# BPF.net
KiCad netlist of a schematic drawn in Altium Designer
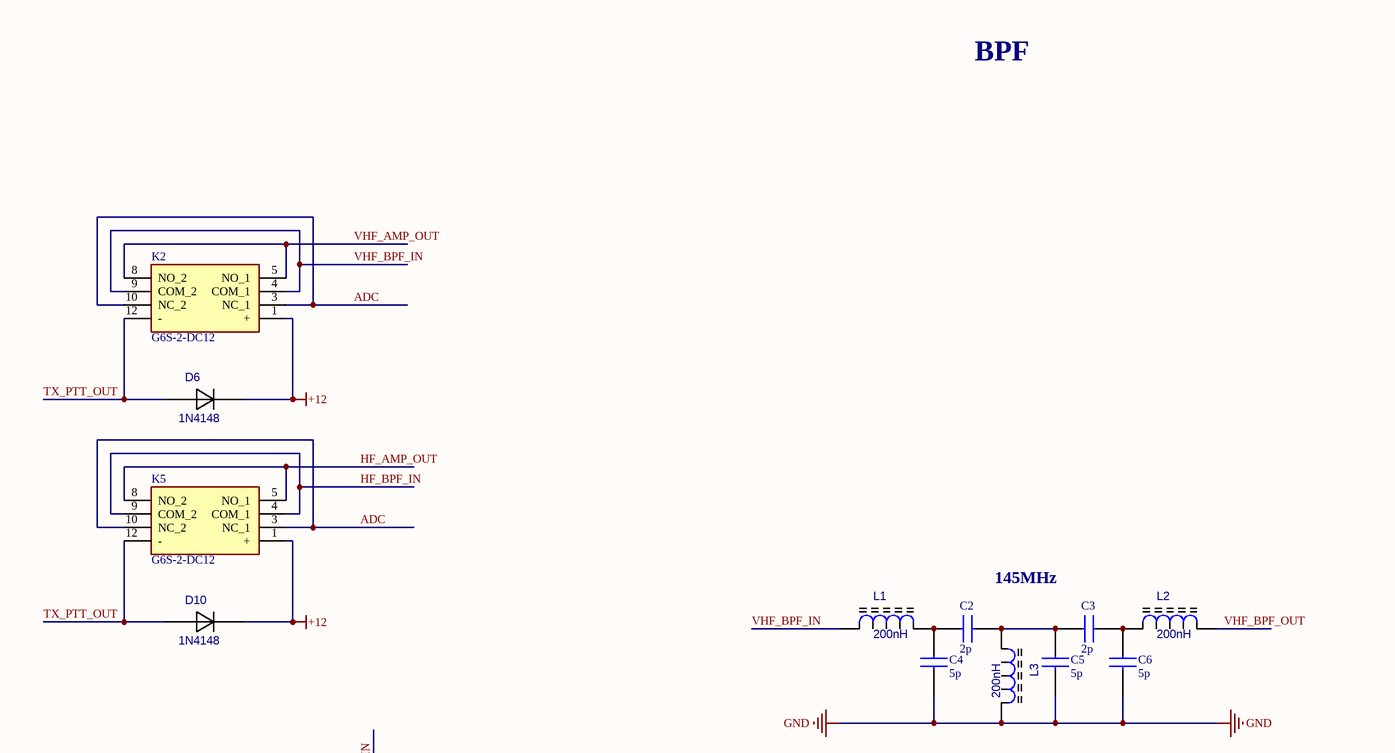
[diagram p0: BPF.SchDoc, top]
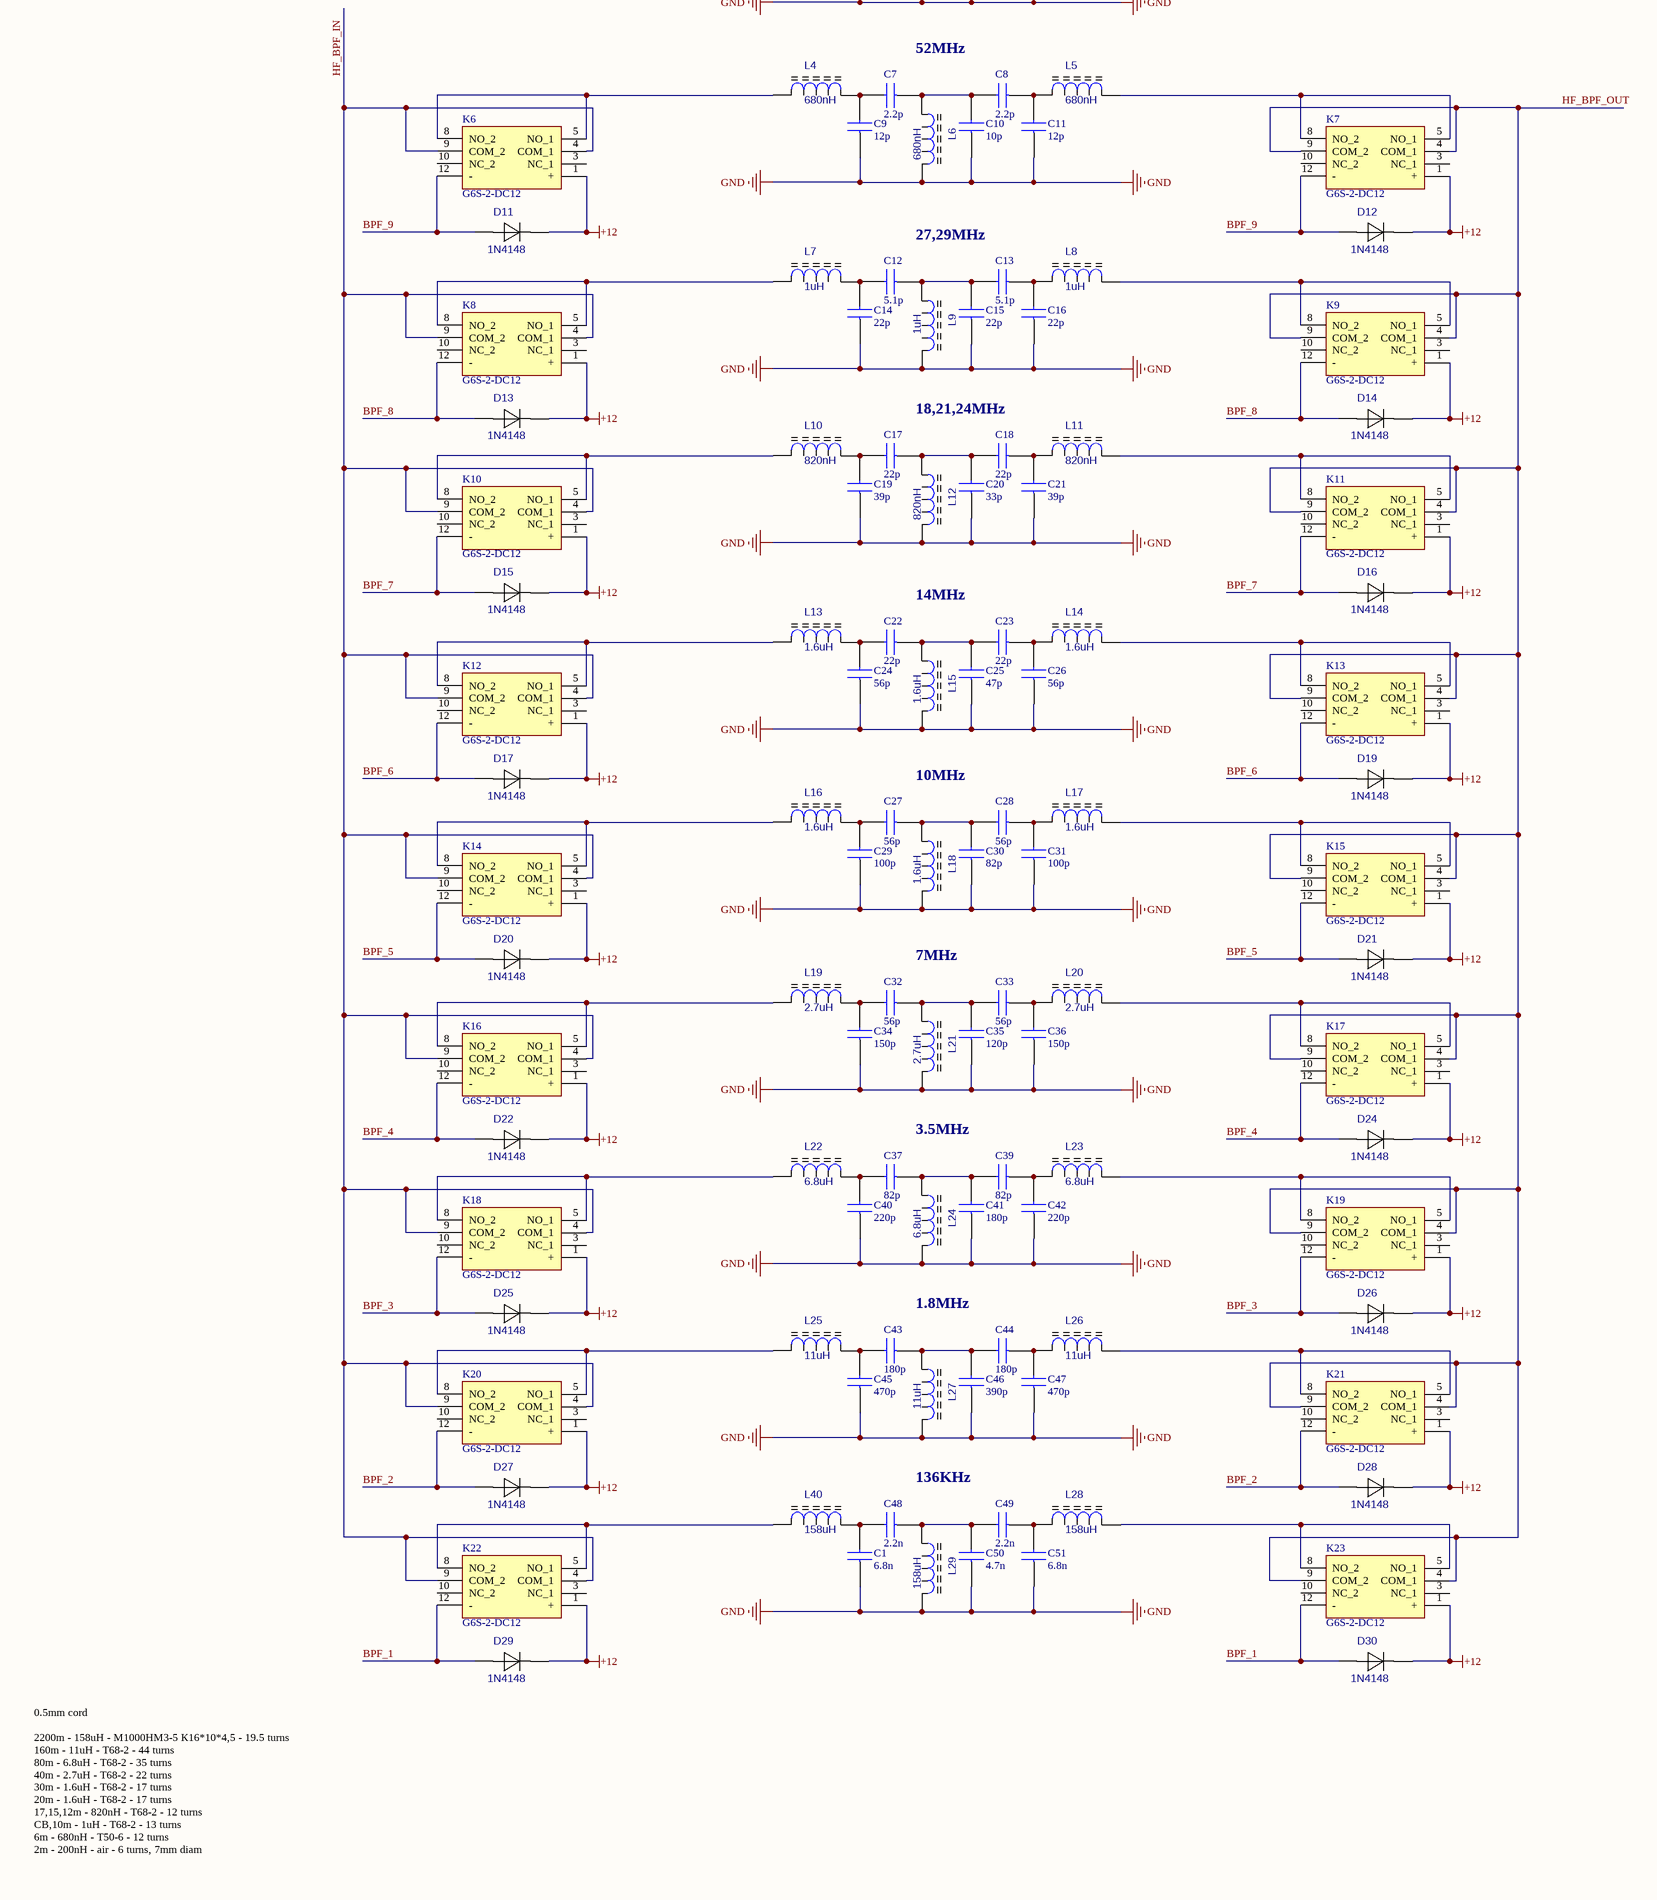
[diagram p1: BPF.SchDoc, bottom]

(export (version "E")
  (design (tool "Eeschema 10.0.6"))
  (components
    (comp (ref "C1")
      (value "6.8n")
      (footprint "CAP_1206")
      (description "Capacitor NP0 HiVolt")
      (fields
        (field (name "MANUFACTURER_PART_NUMBER") "B32620A0682J000")
        (field (name "MOUSER PART NUMBER") "871-B32620A682J")
      )
      (libsource (lib "*") (part "B32620A0682J000"))
    )
    (comp (ref "C2")
      (value "2p")
      (footprint "CAP_1206")
      (description "Capacitor NP0 HiVolt")
      (fields
        (field (name "MANUFACTURER_PART_NUMBER") "B32620A0682J000")
        (field (name "MOUSER PART NUMBER") "871-B32620A682J")
      )
      (libsource (lib "*") (part "B32620A0682J000"))
    )
    (comp (ref "C3")
      (value "2p")
      (footprint "CAP_1206")
      (description "Capacitor NP0 HiVolt")
      (fields
        (field (name "MANUFACTURER_PART_NUMBER") "B32620A0682J000")
        (field (name "MOUSER PART NUMBER") "871-B32620A682J")
      )
      (libsource (lib "*") (part "B32620A0682J000"))
    )
    (comp (ref "C4")
      (value "5p")
      (footprint "CAP_1206")
      (description "Capacitor NP0 HiVolt")
      (fields
        (field (name "MANUFACTURER_PART_NUMBER") "B32620A0682J000")
        (field (name "MOUSER PART NUMBER") "871-B32620A682J")
      )
      (libsource (lib "*") (part "B32620A0682J000"))
    )
    (comp (ref "C5")
      (value "5p")
      (footprint "CAP_1206")
      (description "Capacitor NP0 HiVolt")
      (fields
        (field (name "MANUFACTURER_PART_NUMBER") "B32620A0682J000")
        (field (name "MOUSER PART NUMBER") "871-B32620A682J")
      )
      (libsource (lib "*") (part "B32620A0682J000"))
    )
    (comp (ref "C6")
      (value "5p")
      (footprint "CAP_1206")
      (description "Capacitor NP0 HiVolt")
      (fields
        (field (name "MANUFACTURER_PART_NUMBER") "B32620A0682J000")
        (field (name "MOUSER PART NUMBER") "871-B32620A682J")
      )
      (libsource (lib "*") (part "B32620A0682J000"))
    )
    (comp (ref "C7")
      (value "2.2p")
      (footprint "CAP_1206")
      (description "Capacitor NP0 HiVolt")
      (fields
        (field (name "MANUFACTURER_PART_NUMBER") "B32620A0682J000")
        (field (name "MOUSER PART NUMBER") "871-B32620A682J")
      )
      (libsource (lib "*") (part "B32620A0682J000"))
    )
    (comp (ref "C8")
      (value "2.2p")
      (footprint "CAP_1206")
      (description "Capacitor NP0 HiVolt")
      (fields
        (field (name "MANUFACTURER_PART_NUMBER") "B32620A0682J000")
        (field (name "MOUSER PART NUMBER") "871-B32620A682J")
      )
      (libsource (lib "*") (part "B32620A0682J000"))
    )
    (comp (ref "C9")
      (value "12p")
      (footprint "CAP_1206")
      (description "Capacitor NP0 HiVolt")
      (fields
        (field (name "MANUFACTURER_PART_NUMBER") "B32620A0682J000")
        (field (name "MOUSER PART NUMBER") "871-B32620A682J")
      )
      (libsource (lib "*") (part "B32620A0682J000"))
    )
    (comp (ref "C10")
      (value "10p")
      (footprint "CAP_1206")
      (description "Capacitor NP0 HiVolt")
      (fields
        (field (name "MANUFACTURER_PART_NUMBER") "B32620A0682J000")
        (field (name "MOUSER PART NUMBER") "871-B32620A682J")
      )
      (libsource (lib "*") (part "B32620A0682J000"))
    )
    (comp (ref "C11")
      (value "12p")
      (footprint "CAP_1206")
      (description "Capacitor NP0 HiVolt")
      (fields
        (field (name "MANUFACTURER_PART_NUMBER") "B32620A0682J000")
        (field (name "MOUSER PART NUMBER") "871-B32620A682J")
      )
      (libsource (lib "*") (part "B32620A0682J000"))
    )
    (comp (ref "C12")
      (value "5.1p")
      (footprint "CAP_1206")
      (description "Capacitor NP0 HiVolt")
      (fields
        (field (name "MANUFACTURER_PART_NUMBER") "B32620A0682J000")
        (field (name "MOUSER PART NUMBER") "871-B32620A682J")
      )
      (libsource (lib "*") (part "B32620A0682J000"))
    )
    (comp (ref "C13")
      (value "5.1p")
      (footprint "CAP_1206")
      (description "Capacitor NP0 HiVolt")
      (fields
        (field (name "MANUFACTURER_PART_NUMBER") "B32620A0682J000")
        (field (name "MOUSER PART NUMBER") "871-B32620A682J")
      )
      (libsource (lib "*") (part "B32620A0682J000"))
    )
    (comp (ref "C14")
      (value "22p")
      (footprint "CAP_1206")
      (description "Capacitor NP0 HiVolt")
      (fields
        (field (name "MANUFACTURER_PART_NUMBER") "B32620A0682J000")
        (field (name "MOUSER PART NUMBER") "871-B32620A682J")
      )
      (libsource (lib "*") (part "B32620A0682J000"))
    )
    (comp (ref "C15")
      (value "22p")
      (footprint "CAP_1206")
      (description "Capacitor NP0 HiVolt")
      (fields
        (field (name "MANUFACTURER_PART_NUMBER") "B32620A0682J000")
        (field (name "MOUSER PART NUMBER") "871-B32620A682J")
      )
      (libsource (lib "*") (part "B32620A0682J000"))
    )
    (comp (ref "C16")
      (value "22p")
      (footprint "CAP_1206")
      (description "Capacitor NP0 HiVolt")
      (fields
        (field (name "MANUFACTURER_PART_NUMBER") "B32620A0682J000")
        (field (name "MOUSER PART NUMBER") "871-B32620A682J")
      )
      (libsource (lib "*") (part "B32620A0682J000"))
    )
    (comp (ref "C17")
      (value "22p")
      (footprint "CAP_1206")
      (description "Capacitor NP0 HiVolt")
      (fields
        (field (name "MANUFACTURER_PART_NUMBER") "B32620A0682J000")
        (field (name "MOUSER PART NUMBER") "871-B32620A682J")
      )
      (libsource (lib "*") (part "B32620A0682J000"))
    )
    (comp (ref "C18")
      (value "22p")
      (footprint "CAP_1206")
      (description "Capacitor NP0 HiVolt")
      (fields
        (field (name "MANUFACTURER_PART_NUMBER") "B32620A0682J000")
        (field (name "MOUSER PART NUMBER") "871-B32620A682J")
      )
      (libsource (lib "*") (part "B32620A0682J000"))
    )
    (comp (ref "C19")
      (value "39p")
      (footprint "CAP_1206")
      (description "Capacitor NP0 HiVolt")
      (fields
        (field (name "MANUFACTURER_PART_NUMBER") "B32620A0682J000")
        (field (name "MOUSER PART NUMBER") "871-B32620A682J")
      )
      (libsource (lib "*") (part "B32620A0682J000"))
    )
    (comp (ref "C20")
      (value "33p")
      (footprint "CAP_1206")
      (description "Capacitor NP0 HiVolt")
      (fields
        (field (name "MANUFACTURER_PART_NUMBER") "B32620A0682J000")
        (field (name "MOUSER PART NUMBER") "871-B32620A682J")
      )
      (libsource (lib "*") (part "B32620A0682J000"))
    )
    (comp (ref "C21")
      (value "39p")
      (footprint "CAP_1206")
      (description "Capacitor NP0 HiVolt")
      (fields
        (field (name "MANUFACTURER_PART_NUMBER") "B32620A0682J000")
        (field (name "MOUSER PART NUMBER") "871-B32620A682J")
      )
      (libsource (lib "*") (part "B32620A0682J000"))
    )
    (comp (ref "C22")
      (value "22p")
      (footprint "CAP_1206")
      (description "Capacitor NP0 HiVolt")
      (fields
        (field (name "MANUFACTURER_PART_NUMBER") "B32620A0682J000")
        (field (name "MOUSER PART NUMBER") "871-B32620A682J")
      )
      (libsource (lib "*") (part "B32620A0682J000"))
    )
    (comp (ref "C23")
      (value "22p")
      (footprint "CAP_1206")
      (description "Capacitor NP0 HiVolt")
      (fields
        (field (name "MANUFACTURER_PART_NUMBER") "B32620A0682J000")
        (field (name "MOUSER PART NUMBER") "871-B32620A682J")
      )
      (libsource (lib "*") (part "B32620A0682J000"))
    )
    (comp (ref "C24")
      (value "56p")
      (footprint "CAP_1206")
      (description "Capacitor NP0 HiVolt")
      (fields
        (field (name "MANUFACTURER_PART_NUMBER") "B32620A0682J000")
        (field (name "MOUSER PART NUMBER") "871-B32620A682J")
      )
      (libsource (lib "*") (part "B32620A0682J000"))
    )
    (comp (ref "C25")
      (value "47p")
      (footprint "CAP_1206")
      (description "Capacitor NP0 HiVolt")
      (fields
        (field (name "MANUFACTURER_PART_NUMBER") "B32620A0682J000")
        (field (name "MOUSER PART NUMBER") "871-B32620A682J")
      )
      (libsource (lib "*") (part "B32620A0682J000"))
    )
    (comp (ref "C26")
      (value "56p")
      (footprint "CAP_1206")
      (description "Capacitor NP0 HiVolt")
      (fields
        (field (name "MANUFACTURER_PART_NUMBER") "B32620A0682J000")
        (field (name "MOUSER PART NUMBER") "871-B32620A682J")
      )
      (libsource (lib "*") (part "B32620A0682J000"))
    )
    (comp (ref "C27")
      (value "56p")
      (footprint "CAP_1206")
      (description "Capacitor NP0 HiVolt")
      (fields
        (field (name "MANUFACTURER_PART_NUMBER") "B32620A0682J000")
        (field (name "MOUSER PART NUMBER") "871-B32620A682J")
      )
      (libsource (lib "*") (part "B32620A0682J000"))
    )
    (comp (ref "C28")
      (value "56p")
      (footprint "CAP_1206")
      (description "Capacitor NP0 HiVolt")
      (fields
        (field (name "MANUFACTURER_PART_NUMBER") "B32620A0682J000")
        (field (name "MOUSER PART NUMBER") "871-B32620A682J")
      )
      (libsource (lib "*") (part "B32620A0682J000"))
    )
    (comp (ref "C29")
      (value "100p")
      (footprint "CAP_1206")
      (description "Capacitor NP0 HiVolt")
      (fields
        (field (name "MANUFACTURER_PART_NUMBER") "B32620A0682J000")
        (field (name "MOUSER PART NUMBER") "871-B32620A682J")
      )
      (libsource (lib "*") (part "B32620A0682J000"))
    )
    (comp (ref "C30")
      (value "82p")
      (footprint "CAP_1206")
      (description "Capacitor NP0 HiVolt")
      (fields
        (field (name "MANUFACTURER_PART_NUMBER") "B32620A0682J000")
        (field (name "MOUSER PART NUMBER") "871-B32620A682J")
      )
      (libsource (lib "*") (part "B32620A0682J000"))
    )
    (comp (ref "C31")
      (value "100p")
      (footprint "CAP_1206")
      (description "Capacitor NP0 HiVolt")
      (fields
        (field (name "MANUFACTURER_PART_NUMBER") "B32620A0682J000")
        (field (name "MOUSER PART NUMBER") "871-B32620A682J")
      )
      (libsource (lib "*") (part "B32620A0682J000"))
    )
    (comp (ref "C32")
      (value "56p")
      (footprint "CAP_1206")
      (description "Capacitor NP0 HiVolt")
      (fields
        (field (name "MANUFACTURER_PART_NUMBER") "B32620A0682J000")
        (field (name "MOUSER PART NUMBER") "871-B32620A682J")
      )
      (libsource (lib "*") (part "B32620A0682J000"))
    )
    (comp (ref "C33")
      (value "56p")
      (footprint "CAP_1206")
      (description "Capacitor NP0 HiVolt")
      (fields
        (field (name "MANUFACTURER_PART_NUMBER") "B32620A0682J000")
        (field (name "MOUSER PART NUMBER") "871-B32620A682J")
      )
      (libsource (lib "*") (part "B32620A0682J000"))
    )
    (comp (ref "C34")
      (value "150p")
      (footprint "CAP_1206")
      (description "Capacitor NP0 HiVolt")
      (fields
        (field (name "MANUFACTURER_PART_NUMBER") "B32620A0682J000")
        (field (name "MOUSER PART NUMBER") "871-B32620A682J")
      )
      (libsource (lib "*") (part "B32620A0682J000"))
    )
    (comp (ref "C35")
      (value "120p")
      (footprint "CAP_1206")
      (description "Capacitor NP0 HiVolt")
      (fields
        (field (name "MANUFACTURER_PART_NUMBER") "B32620A0682J000")
        (field (name "MOUSER PART NUMBER") "871-B32620A682J")
      )
      (libsource (lib "*") (part "B32620A0682J000"))
    )
    (comp (ref "C36")
      (value "150p")
      (footprint "CAP_1206")
      (description "Capacitor NP0 HiVolt")
      (fields
        (field (name "MANUFACTURER_PART_NUMBER") "B32620A0682J000")
        (field (name "MOUSER PART NUMBER") "871-B32620A682J")
      )
      (libsource (lib "*") (part "B32620A0682J000"))
    )
    (comp (ref "C37")
      (value "82p")
      (footprint "CAP_1206")
      (description "Capacitor NP0 HiVolt")
      (fields
        (field (name "MANUFACTURER_PART_NUMBER") "B32620A0682J000")
        (field (name "MOUSER PART NUMBER") "871-B32620A682J")
      )
      (libsource (lib "*") (part "B32620A0682J000"))
    )
    (comp (ref "C39")
      (value "82p")
      (footprint "CAP_1206")
      (description "Capacitor NP0 HiVolt")
      (fields
        (field (name "MANUFACTURER_PART_NUMBER") "B32620A0682J000")
        (field (name "MOUSER PART NUMBER") "871-B32620A682J")
      )
      (libsource (lib "*") (part "B32620A0682J000"))
    )
    (comp (ref "C40")
      (value "220p")
      (footprint "CAP_1206")
      (description "Capacitor NP0 HiVolt")
      (fields
        (field (name "MANUFACTURER_PART_NUMBER") "B32620A0682J000")
        (field (name "MOUSER PART NUMBER") "871-B32620A682J")
      )
      (libsource (lib "*") (part "B32620A0682J000"))
    )
    (comp (ref "C41")
      (value "180p")
      (footprint "CAP_1206")
      (description "Capacitor NP0 HiVolt")
      (fields
        (field (name "MANUFACTURER_PART_NUMBER") "B32620A0682J000")
        (field (name "MOUSER PART NUMBER") "871-B32620A682J")
      )
      (libsource (lib "*") (part "B32620A0682J000"))
    )
    (comp (ref "C42")
      (value "220p")
      (footprint "CAP_1206")
      (description "Capacitor NP0 HiVolt")
      (fields
        (field (name "MANUFACTURER_PART_NUMBER") "B32620A0682J000")
        (field (name "MOUSER PART NUMBER") "871-B32620A682J")
      )
      (libsource (lib "*") (part "B32620A0682J000"))
    )
    (comp (ref "C43")
      (value "180p")
      (footprint "CAP_1206")
      (description "Capacitor NP0 HiVolt")
      (fields
        (field (name "MANUFACTURER_PART_NUMBER") "B32620A0682J000")
        (field (name "MOUSER PART NUMBER") "871-B32620A682J")
      )
      (libsource (lib "*") (part "B32620A0682J000"))
    )
    (comp (ref "C44")
      (value "180p")
      (footprint "CAP_1206")
      (description "Capacitor NP0 HiVolt")
      (fields
        (field (name "MANUFACTURER_PART_NUMBER") "B32620A0682J000")
        (field (name "MOUSER PART NUMBER") "871-B32620A682J")
      )
      (libsource (lib "*") (part "B32620A0682J000"))
    )
    (comp (ref "C45")
      (value "470p")
      (footprint "CAP_1206")
      (description "Capacitor NP0 HiVolt")
      (fields
        (field (name "MANUFACTURER_PART_NUMBER") "B32620A0682J000")
        (field (name "MOUSER PART NUMBER") "871-B32620A682J")
      )
      (libsource (lib "*") (part "B32620A0682J000"))
    )
    (comp (ref "C46")
      (value "390p")
      (footprint "CAP_1206")
      (description "Capacitor NP0 HiVolt")
      (fields
        (field (name "MANUFACTURER_PART_NUMBER") "B32620A0682J000")
        (field (name "MOUSER PART NUMBER") "871-B32620A682J")
      )
      (libsource (lib "*") (part "B32620A0682J000"))
    )
    (comp (ref "C47")
      (value "470p")
      (footprint "CAP_1206")
      (description "Capacitor NP0 HiVolt")
      (fields
        (field (name "MANUFACTURER_PART_NUMBER") "B32620A0682J000")
        (field (name "MOUSER PART NUMBER") "871-B32620A682J")
      )
      (libsource (lib "*") (part "B32620A0682J000"))
    )
    (comp (ref "C48")
      (value "2.2n")
      (footprint "CAP_1206")
      (description "Capacitor NP0 HiVolt")
      (fields
        (field (name "MANUFACTURER_PART_NUMBER") "B32620A0682J000")
        (field (name "MOUSER PART NUMBER") "871-B32620A682J")
      )
      (libsource (lib "*") (part "B32620A0682J000"))
    )
    (comp (ref "C49")
      (value "2.2n")
      (footprint "CAP_1206")
      (description "Capacitor NP0 HiVolt")
      (fields
        (field (name "MANUFACTURER_PART_NUMBER") "B32620A0682J000")
        (field (name "MOUSER PART NUMBER") "871-B32620A682J")
      )
      (libsource (lib "*") (part "B32620A0682J000"))
    )
    (comp (ref "C50")
      (value "4.7n")
      (footprint "CAP_1206")
      (description "Capacitor NP0 HiVolt")
      (fields
        (field (name "MANUFACTURER_PART_NUMBER") "B32620A0682J000")
        (field (name "MOUSER PART NUMBER") "871-B32620A682J")
      )
      (libsource (lib "*") (part "B32620A0682J000"))
    )
    (comp (ref "C51")
      (value "6.8n")
      (footprint "CAP_1206")
      (description "Capacitor NP0 HiVolt")
      (fields
        (field (name "MANUFACTURER_PART_NUMBER") "B32620A0682J000")
        (field (name "MOUSER PART NUMBER") "871-B32620A682J")
      )
      (libsource (lib "*") (part "B32620A0682J000"))
    )
    (comp (ref "D6") (value "1N4148") (footprint "SS14") (libsource (lib "RF-UNIT-BIG") (part "1N4148")))
    (comp (ref "D10") (value "1N4148") (footprint "SS14") (libsource (lib "RF-UNIT-BIG") (part "1N4148")))
    (comp (ref "D11") (value "1N4148") (footprint "SS14") (libsource (lib "RF-UNIT-BIG") (part "1N4148")))
    (comp (ref "D12") (value "1N4148") (footprint "SS14") (libsource (lib "RF-UNIT-BIG") (part "1N4148")))
    (comp (ref "D13") (value "1N4148") (footprint "SS14") (libsource (lib "RF-UNIT-BIG") (part "1N4148")))
    (comp (ref "D14") (value "1N4148") (footprint "SS14") (libsource (lib "RF-UNIT-BIG") (part "1N4148")))
    (comp (ref "D15") (value "1N4148") (footprint "SS14") (libsource (lib "RF-UNIT-BIG") (part "1N4148")))
    (comp (ref "D16") (value "1N4148") (footprint "SS14") (libsource (lib "RF-UNIT-BIG") (part "1N4148")))
    (comp (ref "D17") (value "1N4148") (footprint "SS14") (libsource (lib "RF-UNIT-BIG") (part "1N4148")))
    (comp (ref "D19") (value "1N4148") (footprint "SS14") (libsource (lib "RF-UNIT-BIG") (part "1N4148")))
    (comp (ref "D20") (value "1N4148") (footprint "SS14") (libsource (lib "RF-UNIT-BIG") (part "1N4148")))
    (comp (ref "D21") (value "1N4148") (footprint "SS14") (libsource (lib "RF-UNIT-BIG") (part "1N4148")))
    (comp (ref "D22") (value "1N4148") (footprint "SS14") (libsource (lib "RF-UNIT-BIG") (part "1N4148")))
    (comp (ref "D24") (value "1N4148") (footprint "SS14") (libsource (lib "RF-UNIT-BIG") (part "1N4148")))
    (comp (ref "D25") (value "1N4148") (footprint "SS14") (libsource (lib "RF-UNIT-BIG") (part "1N4148")))
    (comp (ref "D26") (value "1N4148") (footprint "SS14") (libsource (lib "RF-UNIT-BIG") (part "1N4148")))
    (comp (ref "D27") (value "1N4148") (footprint "SS14") (libsource (lib "RF-UNIT-BIG") (part "1N4148")))
    (comp (ref "D28") (value "1N4148") (footprint "SS14") (libsource (lib "RF-UNIT-BIG") (part "1N4148")))
    (comp (ref "D29") (value "1N4148") (footprint "SS14") (libsource (lib "RF-UNIT-BIG") (part "1N4148")))
    (comp (ref "D30") (value "1N4148") (footprint "SS14") (libsource (lib "RF-UNIT-BIG") (part "1N4148")))
    (comp (ref "K2")
      (value "G6S-2-DC12")
      (footprint "SamacSys:G6S2DC12")
      (description "Relay or Contactor")
      (fields (field (name "MOUSER PART NUMBER") "653-G6S-2-DC12A"))
      (libsource (lib "*") (part "G6S-2-DC12"))
    )
    (comp (ref "K5")
      (value "G6S-2-DC12")
      (footprint "SamacSys:G6S2DC12")
      (description "Relay or Contactor")
      (fields (field (name "MOUSER PART NUMBER") "653-G6S-2-DC12A"))
      (libsource (lib "*") (part "G6S-2-DC12"))
    )
    (comp (ref "K6")
      (value "G6S-2-DC12")
      (footprint "SamacSys:G6S2DC12")
      (description "Relay or Contactor")
      (fields (field (name "MOUSER PART NUMBER") "653-G6S-2-DC12A"))
      (libsource (lib "*") (part "G6S-2-DC12"))
    )
    (comp (ref "K7")
      (value "G6S-2-DC12")
      (footprint "SamacSys:G6S2DC12")
      (description "Relay or Contactor")
      (fields (field (name "MOUSER PART NUMBER") "653-G6S-2-DC12A"))
      (libsource (lib "*") (part "G6S-2-DC12"))
    )
    (comp (ref "K8")
      (value "G6S-2-DC12")
      (footprint "SamacSys:G6S2DC12")
      (description "Relay or Contactor")
      (fields (field (name "MOUSER PART NUMBER") "653-G6S-2-DC12A"))
      (libsource (lib "*") (part "G6S-2-DC12"))
    )
    (comp (ref "K9")
      (value "G6S-2-DC12")
      (footprint "SamacSys:G6S2DC12")
      (description "Relay or Contactor")
      (fields (field (name "MOUSER PART NUMBER") "653-G6S-2-DC12A"))
      (libsource (lib "*") (part "G6S-2-DC12"))
    )
    (comp (ref "K10")
      (value "G6S-2-DC12")
      (footprint "SamacSys:G6S2DC12")
      (description "Relay or Contactor")
      (fields (field (name "MOUSER PART NUMBER") "653-G6S-2-DC12A"))
      (libsource (lib "*") (part "G6S-2-DC12"))
    )
    (comp (ref "K11")
      (value "G6S-2-DC12")
      (footprint "SamacSys:G6S2DC12")
      (description "Relay or Contactor")
      (fields (field (name "MOUSER PART NUMBER") "653-G6S-2-DC12A"))
      (libsource (lib "*") (part "G6S-2-DC12"))
    )
    (comp (ref "K12")
      (value "G6S-2-DC12")
      (footprint "SamacSys:G6S2DC12")
      (description "Relay or Contactor")
      (fields (field (name "MOUSER PART NUMBER") "653-G6S-2-DC12A"))
      (libsource (lib "*") (part "G6S-2-DC12"))
    )
    (comp (ref "K13")
      (value "G6S-2-DC12")
      (footprint "SamacSys:G6S2DC12")
      (description "Relay or Contactor")
      (fields (field (name "MOUSER PART NUMBER") "653-G6S-2-DC12A"))
      (libsource (lib "*") (part "G6S-2-DC12"))
    )
    (comp (ref "K14")
      (value "G6S-2-DC12")
      (footprint "SamacSys:G6S2DC12")
      (description "Relay or Contactor")
      (fields (field (name "MOUSER PART NUMBER") "653-G6S-2-DC12A"))
      (libsource (lib "*") (part "G6S-2-DC12"))
    )
    (comp (ref "K15")
      (value "G6S-2-DC12")
      (footprint "SamacSys:G6S2DC12")
      (description "Relay or Contactor")
      (fields (field (name "MOUSER PART NUMBER") "653-G6S-2-DC12A"))
      (libsource (lib "*") (part "G6S-2-DC12"))
    )
    (comp (ref "K16")
      (value "G6S-2-DC12")
      (footprint "SamacSys:G6S2DC12")
      (description "Relay or Contactor")
      (fields (field (name "MOUSER PART NUMBER") "653-G6S-2-DC12A"))
      (libsource (lib "*") (part "G6S-2-DC12"))
    )
    (comp (ref "K17")
      (value "G6S-2-DC12")
      (footprint "SamacSys:G6S2DC12")
      (description "Relay or Contactor")
      (fields (field (name "MOUSER PART NUMBER") "653-G6S-2-DC12A"))
      (libsource (lib "*") (part "G6S-2-DC12"))
    )
    (comp (ref "K18")
      (value "G6S-2-DC12")
      (footprint "SamacSys:G6S2DC12")
      (description "Relay or Contactor")
      (fields (field (name "MOUSER PART NUMBER") "653-G6S-2-DC12A"))
      (libsource (lib "*") (part "G6S-2-DC12"))
    )
    (comp (ref "K19")
      (value "G6S-2-DC12")
      (footprint "SamacSys:G6S2DC12")
      (description "Relay or Contactor")
      (fields (field (name "MOUSER PART NUMBER") "653-G6S-2-DC12A"))
      (libsource (lib "*") (part "G6S-2-DC12"))
    )
    (comp (ref "K20")
      (value "G6S-2-DC12")
      (footprint "SamacSys:G6S2DC12")
      (description "Relay or Contactor")
      (fields (field (name "MOUSER PART NUMBER") "653-G6S-2-DC12A"))
      (libsource (lib "*") (part "G6S-2-DC12"))
    )
    (comp (ref "K21")
      (value "G6S-2-DC12")
      (footprint "SamacSys:G6S2DC12")
      (description "Relay or Contactor")
      (fields (field (name "MOUSER PART NUMBER") "653-G6S-2-DC12A"))
      (libsource (lib "*") (part "G6S-2-DC12"))
    )
    (comp (ref "K22")
      (value "G6S-2-DC12")
      (footprint "SamacSys:G6S2DC12")
      (description "Relay or Contactor")
      (fields (field (name "MOUSER PART NUMBER") "653-G6S-2-DC12A"))
      (libsource (lib "*") (part "G6S-2-DC12"))
    )
    (comp (ref "K23")
      (value "G6S-2-DC12")
      (footprint "SamacSys:G6S2DC12")
      (description "Relay or Contactor")
      (fields (field (name "MOUSER PART NUMBER") "653-G6S-2-DC12A"))
      (libsource (lib "*") (part "G6S-2-DC12"))
    )
    (comp (ref "L1")
      (value "200nH")
      (footprint "IND_FERRITE_CORE_1")
      (description "Inductor")
      (libsource (lib "*") (part "IND_FERRITE_CORE"))
    )
    (comp (ref "L2")
      (value "200nH")
      (footprint "IND_FERRITE_CORE_1")
      (description "Inductor")
      (libsource (lib "*") (part "IND_FERRITE_CORE"))
    )
    (comp (ref "L3")
      (value "200nH")
      (footprint "IND_FERRITE_CORE_1")
      (description "Inductor")
      (libsource (lib "*") (part "IND_FERRITE_CORE"))
    )
    (comp (ref "L4")
      (value "680nH")
      (footprint "IND_FERRITE_CORE_1")
      (description "Inductor")
      (libsource (lib "*") (part "IND_FERRITE_CORE"))
    )
    (comp (ref "L5")
      (value "680nH")
      (footprint "IND_FERRITE_CORE_1")
      (description "Inductor")
      (libsource (lib "*") (part "IND_FERRITE_CORE"))
    )
    (comp (ref "L6")
      (value "680nH")
      (footprint "IND_FERRITE_CORE_1")
      (description "Inductor")
      (libsource (lib "*") (part "IND_FERRITE_CORE"))
    )
    (comp (ref "L7")
      (value "1uH")
      (footprint "IND_FERRITE_CORE_1")
      (description "Inductor")
      (libsource (lib "*") (part "IND_FERRITE_CORE"))
    )
    (comp (ref "L8")
      (value "1uH")
      (footprint "IND_FERRITE_CORE_1")
      (description "Inductor")
      (libsource (lib "*") (part "IND_FERRITE_CORE"))
    )
    (comp (ref "L9")
      (value "1uH")
      (footprint "IND_FERRITE_CORE_1")
      (description "Inductor")
      (libsource (lib "*") (part "IND_FERRITE_CORE"))
    )
    (comp (ref "L10")
      (value "820nH")
      (footprint "IND_FERRITE_CORE_1")
      (description "Inductor")
      (libsource (lib "*") (part "IND_FERRITE_CORE"))
    )
    (comp (ref "L11")
      (value "820nH")
      (footprint "IND_FERRITE_CORE_1")
      (description "Inductor")
      (libsource (lib "*") (part "IND_FERRITE_CORE"))
    )
    (comp (ref "L12")
      (value "820nH")
      (footprint "IND_FERRITE_CORE_1")
      (description "Inductor")
      (libsource (lib "*") (part "IND_FERRITE_CORE"))
    )
    (comp (ref "L13")
      (value "1.6uH")
      (footprint "IND_FERRITE_CORE_1")
      (description "Inductor")
      (libsource (lib "*") (part "IND_FERRITE_CORE"))
    )
    (comp (ref "L14")
      (value "1.6uH")
      (footprint "IND_FERRITE_CORE_1")
      (description "Inductor")
      (libsource (lib "*") (part "IND_FERRITE_CORE"))
    )
    (comp (ref "L15")
      (value "1.6uH")
      (footprint "IND_FERRITE_CORE_1")
      (description "Inductor")
      (libsource (lib "*") (part "IND_FERRITE_CORE"))
    )
    (comp (ref "L16")
      (value "1.6uH")
      (footprint "IND_FERRITE_CORE_1")
      (description "Inductor")
      (libsource (lib "*") (part "IND_FERRITE_CORE"))
    )
    (comp (ref "L17")
      (value "1.6uH")
      (footprint "IND_FERRITE_CORE_1")
      (description "Inductor")
      (libsource (lib "*") (part "IND_FERRITE_CORE"))
    )
    (comp (ref "L18")
      (value "1.6uH")
      (footprint "IND_FERRITE_CORE_1")
      (description "Inductor")
      (libsource (lib "*") (part "IND_FERRITE_CORE"))
    )
    (comp (ref "L19")
      (value "2.7uH")
      (footprint "IND_FERRITE_CORE_1")
      (description "Inductor")
      (libsource (lib "*") (part "IND_FERRITE_CORE"))
    )
    (comp (ref "L20")
      (value "2.7uH")
      (footprint "IND_FERRITE_CORE_1")
      (description "Inductor")
      (libsource (lib "*") (part "IND_FERRITE_CORE"))
    )
    (comp (ref "L21")
      (value "2.7uH")
      (footprint "IND_FERRITE_CORE_1")
      (description "Inductor")
      (libsource (lib "*") (part "IND_FERRITE_CORE"))
    )
    (comp (ref "L22")
      (value "6.8uH")
      (footprint "IND_FERRITE_CORE_1")
      (description "Inductor")
      (libsource (lib "*") (part "IND_FERRITE_CORE"))
    )
    (comp (ref "L23")
      (value "6.8uH")
      (footprint "IND_FERRITE_CORE_1")
      (description "Inductor")
      (libsource (lib "*") (part "IND_FERRITE_CORE"))
    )
    (comp (ref "L24")
      (value "6.8uH")
      (footprint "IND_FERRITE_CORE_1")
      (description "Inductor")
      (libsource (lib "*") (part "IND_FERRITE_CORE"))
    )
    (comp (ref "L25")
      (value "11uH")
      (footprint "IND_FERRITE_CORE_1")
      (description "Inductor")
      (libsource (lib "*") (part "IND_FERRITE_CORE"))
    )
    (comp (ref "L26")
      (value "11uH")
      (footprint "IND_FERRITE_CORE_1")
      (description "Inductor")
      (libsource (lib "*") (part "IND_FERRITE_CORE"))
    )
    (comp (ref "L27")
      (value "11uH")
      (footprint "IND_FERRITE_CORE_1")
      (description "Inductor")
      (libsource (lib "*") (part "IND_FERRITE_CORE"))
    )
    (comp (ref "L28")
      (value "158uH")
      (footprint "IND_FERRITE_CORE_1")
      (description "Inductor")
      (libsource (lib "*") (part "IND_FERRITE_CORE"))
    )
    (comp (ref "L29")
      (value "158uH")
      (footprint "IND_FERRITE_CORE_1")
      (description "Inductor")
      (libsource (lib "*") (part "IND_FERRITE_CORE"))
    )
    (comp (ref "L40")
      (value "158uH")
      (footprint "IND_FERRITE_CORE_1")
      (description "Inductor")
      (libsource (lib "*") (part "IND_FERRITE_CORE"))
    )
  )
  (nets
    (net (code "1") (name "+12") (class "Default")
      (node (ref "D10") (pin "1") (pinfunction "K_1") (pintype "passive"))
      (node (ref "D11") (pin "1") (pinfunction "K_1") (pintype "passive"))
      (node (ref "D12") (pin "1") (pinfunction "K_1") (pintype "passive"))
      (node (ref "D13") (pin "1") (pinfunction "K_1") (pintype "passive"))
      (node (ref "D14") (pin "1") (pinfunction "K_1") (pintype "passive"))
      (node (ref "D15") (pin "1") (pinfunction "K_1") (pintype "passive"))
      (node (ref "D16") (pin "1") (pinfunction "K_1") (pintype "passive"))
      (node (ref "D17") (pin "1") (pinfunction "K_1") (pintype "passive"))
      (node (ref "D19") (pin "1") (pinfunction "K_1") (pintype "passive"))
      (node (ref "D20") (pin "1") (pinfunction "K_1") (pintype "passive"))
      (node (ref "D21") (pin "1") (pinfunction "K_1") (pintype "passive"))
      (node (ref "D22") (pin "1") (pinfunction "K_1") (pintype "passive"))
      (node (ref "D24") (pin "1") (pinfunction "K_1") (pintype "passive"))
      (node (ref "D25") (pin "1") (pinfunction "K_1") (pintype "passive"))
      (node (ref "D26") (pin "1") (pinfunction "K_1") (pintype "passive"))
      (node (ref "D27") (pin "1") (pinfunction "K_1") (pintype "passive"))
      (node (ref "D28") (pin "1") (pinfunction "K_1") (pintype "passive"))
      (node (ref "D29") (pin "1") (pinfunction "K_1") (pintype "passive"))
      (node (ref "D30") (pin "1") (pinfunction "K_1") (pintype "passive"))
      (node (ref "D6") (pin "1") (pinfunction "K_1") (pintype "passive"))
      (node (ref "K10") (pin "1") (pinfunction "+_1") (pintype "passive"))
      (node (ref "K11") (pin "1") (pinfunction "+_1") (pintype "passive"))
      (node (ref "K12") (pin "1") (pinfunction "+_1") (pintype "passive"))
      (node (ref "K13") (pin "1") (pinfunction "+_1") (pintype "passive"))
      (node (ref "K14") (pin "1") (pinfunction "+_1") (pintype "passive"))
      (node (ref "K15") (pin "1") (pinfunction "+_1") (pintype "passive"))
      (node (ref "K16") (pin "1") (pinfunction "+_1") (pintype "passive"))
      (node (ref "K17") (pin "1") (pinfunction "+_1") (pintype "passive"))
      (node (ref "K18") (pin "1") (pinfunction "+_1") (pintype "passive"))
      (node (ref "K19") (pin "1") (pinfunction "+_1") (pintype "passive"))
      (node (ref "K2") (pin "1") (pinfunction "+_1") (pintype "passive"))
      (node (ref "K20") (pin "1") (pinfunction "+_1") (pintype "passive"))
      (node (ref "K21") (pin "1") (pinfunction "+_1") (pintype "passive"))
      (node (ref "K22") (pin "1") (pinfunction "+_1") (pintype "passive"))
      (node (ref "K23") (pin "1") (pinfunction "+_1") (pintype "passive"))
      (node (ref "K5") (pin "1") (pinfunction "+_1") (pintype "passive"))
      (node (ref "K6") (pin "1") (pinfunction "+_1") (pintype "passive"))
      (node (ref "K7") (pin "1") (pinfunction "+_1") (pintype "passive"))
      (node (ref "K8") (pin "1") (pinfunction "+_1") (pintype "passive"))
      (node (ref "K9") (pin "1") (pinfunction "+_1") (pintype "passive"))
    )
    (net (code "2") (name "/ADC") (class "Default")
      (node (ref "K2") (pin "10") (pinfunction "NC_2_10") (pintype "passive"))
      (node (ref "K2") (pin "3") (pinfunction "NC_1_3") (pintype "passive"))
      (node (ref "K5") (pin "10") (pinfunction "NC_2_10") (pintype "passive"))
      (node (ref "K5") (pin "3") (pinfunction "NC_1_3") (pintype "passive"))
    )
    (net (code "3") (name "/BPF_1") (class "Default")
      (node (ref "D29") (pin "2") (pinfunction "A_2") (pintype "passive"))
      (node (ref "D30") (pin "2") (pinfunction "A_2") (pintype "passive"))
      (node (ref "K22") (pin "12") (pinfunction "-_12") (pintype "passive"))
      (node (ref "K23") (pin "12") (pinfunction "-_12") (pintype "passive"))
    )
    (net (code "4") (name "/BPF_2") (class "Default")
      (node (ref "D27") (pin "2") (pinfunction "A_2") (pintype "passive"))
      (node (ref "D28") (pin "2") (pinfunction "A_2") (pintype "passive"))
      (node (ref "K20") (pin "12") (pinfunction "-_12") (pintype "passive"))
      (node (ref "K21") (pin "12") (pinfunction "-_12") (pintype "passive"))
    )
    (net (code "5") (name "/BPF_3") (class "Default")
      (node (ref "D25") (pin "2") (pinfunction "A_2") (pintype "passive"))
      (node (ref "D26") (pin "2") (pinfunction "A_2") (pintype "passive"))
      (node (ref "K18") (pin "12") (pinfunction "-_12") (pintype "passive"))
      (node (ref "K19") (pin "12") (pinfunction "-_12") (pintype "passive"))
    )
    (net (code "6") (name "/BPF_4") (class "Default")
      (node (ref "D22") (pin "2") (pinfunction "A_2") (pintype "passive"))
      (node (ref "D24") (pin "2") (pinfunction "A_2") (pintype "passive"))
      (node (ref "K16") (pin "12") (pinfunction "-_12") (pintype "passive"))
      (node (ref "K17") (pin "12") (pinfunction "-_12") (pintype "passive"))
    )
    (net (code "7") (name "/BPF_5") (class "Default")
      (node (ref "D20") (pin "2") (pinfunction "A_2") (pintype "passive"))
      (node (ref "D21") (pin "2") (pinfunction "A_2") (pintype "passive"))
      (node (ref "K14") (pin "12") (pinfunction "-_12") (pintype "passive"))
      (node (ref "K15") (pin "12") (pinfunction "-_12") (pintype "passive"))
    )
    (net (code "8") (name "/BPF_6") (class "Default")
      (node (ref "D17") (pin "2") (pinfunction "A_2") (pintype "passive"))
      (node (ref "D19") (pin "2") (pinfunction "A_2") (pintype "passive"))
      (node (ref "K12") (pin "12") (pinfunction "-_12") (pintype "passive"))
      (node (ref "K13") (pin "12") (pinfunction "-_12") (pintype "passive"))
    )
    (net (code "9") (name "/BPF_7") (class "Default")
      (node (ref "D15") (pin "2") (pinfunction "A_2") (pintype "passive"))
      (node (ref "D16") (pin "2") (pinfunction "A_2") (pintype "passive"))
      (node (ref "K10") (pin "12") (pinfunction "-_12") (pintype "passive"))
      (node (ref "K11") (pin "12") (pinfunction "-_12") (pintype "passive"))
    )
    (net (code "10") (name "/BPF_8") (class "Default")
      (node (ref "D13") (pin "2") (pinfunction "A_2") (pintype "passive"))
      (node (ref "D14") (pin "2") (pinfunction "A_2") (pintype "passive"))
      (node (ref "K8") (pin "12") (pinfunction "-_12") (pintype "passive"))
      (node (ref "K9") (pin "12") (pinfunction "-_12") (pintype "passive"))
    )
    (net (code "11") (name "/BPF_9") (class "Default")
      (node (ref "D11") (pin "2") (pinfunction "A_2") (pintype "passive"))
      (node (ref "D12") (pin "2") (pinfunction "A_2") (pintype "passive"))
      (node (ref "K6") (pin "12") (pinfunction "-_12") (pintype "passive"))
      (node (ref "K7") (pin "12") (pinfunction "-_12") (pintype "passive"))
    )
    (net (code "12") (name "/HF_AMP_OUT") (class "Default")
      (node (ref "K5") (pin "5") (pinfunction "NO_1_5") (pintype "passive"))
      (node (ref "K5") (pin "8") (pinfunction "NO_2_8") (pintype "passive"))
    )
    (net (code "13") (name "/HF_BPF_IN") (class "Default")
      (node (ref "K10") (pin "4") (pinfunction "COM_1_4") (pintype "passive"))
      (node (ref "K10") (pin "9") (pinfunction "COM_2_9") (pintype "passive"))
      (node (ref "K12") (pin "4") (pinfunction "COM_1_4") (pintype "passive"))
      (node (ref "K12") (pin "9") (pinfunction "COM_2_9") (pintype "passive"))
      (node (ref "K14") (pin "4") (pinfunction "COM_1_4") (pintype "passive"))
      (node (ref "K14") (pin "9") (pinfunction "COM_2_9") (pintype "passive"))
      (node (ref "K16") (pin "4") (pinfunction "COM_1_4") (pintype "passive"))
      (node (ref "K16") (pin "9") (pinfunction "COM_2_9") (pintype "passive"))
      (node (ref "K18") (pin "4") (pinfunction "COM_1_4") (pintype "passive"))
      (node (ref "K18") (pin "9") (pinfunction "COM_2_9") (pintype "passive"))
      (node (ref "K20") (pin "4") (pinfunction "COM_1_4") (pintype "passive"))
      (node (ref "K20") (pin "9") (pinfunction "COM_2_9") (pintype "passive"))
      (node (ref "K22") (pin "4") (pinfunction "COM_1_4") (pintype "passive"))
      (node (ref "K22") (pin "9") (pinfunction "COM_2_9") (pintype "passive"))
      (node (ref "K5") (pin "4") (pinfunction "COM_1_4") (pintype "passive"))
      (node (ref "K5") (pin "9") (pinfunction "COM_2_9") (pintype "passive"))
      (node (ref "K6") (pin "4") (pinfunction "COM_1_4") (pintype "passive"))
      (node (ref "K6") (pin "9") (pinfunction "COM_2_9") (pintype "passive"))
      (node (ref "K8") (pin "4") (pinfunction "COM_1_4") (pintype "passive"))
      (node (ref "K8") (pin "9") (pinfunction "COM_2_9") (pintype "passive"))
    )
    (net (code "14") (name "/HF_BPF_OUT") (class "Default")
      (node (ref "K11") (pin "4") (pinfunction "COM_1_4") (pintype "passive"))
      (node (ref "K11") (pin "9") (pinfunction "COM_2_9") (pintype "passive"))
      (node (ref "K13") (pin "4") (pinfunction "COM_1_4") (pintype "passive"))
      (node (ref "K13") (pin "9") (pinfunction "COM_2_9") (pintype "passive"))
      (node (ref "K15") (pin "4") (pinfunction "COM_1_4") (pintype "passive"))
      (node (ref "K15") (pin "9") (pinfunction "COM_2_9") (pintype "passive"))
      (node (ref "K17") (pin "4") (pinfunction "COM_1_4") (pintype "passive"))
      (node (ref "K17") (pin "9") (pinfunction "COM_2_9") (pintype "passive"))
      (node (ref "K19") (pin "4") (pinfunction "COM_1_4") (pintype "passive"))
      (node (ref "K19") (pin "9") (pinfunction "COM_2_9") (pintype "passive"))
      (node (ref "K21") (pin "4") (pinfunction "COM_1_4") (pintype "passive"))
      (node (ref "K21") (pin "9") (pinfunction "COM_2_9") (pintype "passive"))
      (node (ref "K23") (pin "4") (pinfunction "COM_1_4") (pintype "passive"))
      (node (ref "K23") (pin "9") (pinfunction "COM_2_9") (pintype "passive"))
      (node (ref "K7") (pin "4") (pinfunction "COM_1_4") (pintype "passive"))
      (node (ref "K7") (pin "9") (pinfunction "COM_2_9") (pintype "passive"))
      (node (ref "K9") (pin "4") (pinfunction "COM_1_4") (pintype "passive"))
      (node (ref "K9") (pin "9") (pinfunction "COM_2_9") (pintype "passive"))
    )
    (net (code "15") (name "/TX_PTT_OUT") (class "Default")
      (node (ref "D10") (pin "2") (pinfunction "A_2") (pintype "passive"))
      (node (ref "D6") (pin "2") (pinfunction "A_2") (pintype "passive"))
      (node (ref "K2") (pin "12") (pinfunction "-_12") (pintype "passive"))
      (node (ref "K5") (pin "12") (pinfunction "-_12") (pintype "passive"))
    )
    (net (code "16") (name "/VHF_AMP_OUT") (class "Default")
      (node (ref "K2") (pin "5") (pinfunction "NO_1_5") (pintype "passive"))
      (node (ref "K2") (pin "8") (pinfunction "NO_2_8") (pintype "passive"))
    )
    (net (code "17") (name "/VHF_BPF_IN") (class "Default")
      (node (ref "K2") (pin "4") (pinfunction "COM_1_4") (pintype "passive"))
      (node (ref "K2") (pin "9") (pinfunction "COM_2_9") (pintype "passive"))
      (node (ref "L1") (pin "1") (pinfunction "A_1") (pintype "passive"))
    )
    (net (code "18") (name "/VHF_BPF_OUT") (class "Default")
      (node (ref "L2") (pin "2") (pinfunction "B_2") (pintype "passive"))
    )
    (net (code "19") (name "GND") (class "Default")
      (node (ref "C1") (pin "1") (pinfunction "1_1") (pintype "passive"))
      (node (ref "C10") (pin "1") (pinfunction "1_1") (pintype "passive"))
      (node (ref "C11") (pin "1") (pinfunction "1_1") (pintype "passive"))
      (node (ref "C14") (pin "1") (pinfunction "1_1") (pintype "passive"))
      (node (ref "C15") (pin "1") (pinfunction "1_1") (pintype "passive"))
      (node (ref "C16") (pin "1") (pinfunction "1_1") (pintype "passive"))
      (node (ref "C19") (pin "1") (pinfunction "1_1") (pintype "passive"))
      (node (ref "C20") (pin "1") (pinfunction "1_1") (pintype "passive"))
      (node (ref "C21") (pin "1") (pinfunction "1_1") (pintype "passive"))
      (node (ref "C24") (pin "1") (pinfunction "1_1") (pintype "passive"))
      (node (ref "C25") (pin "1") (pinfunction "1_1") (pintype "passive"))
      (node (ref "C26") (pin "1") (pinfunction "1_1") (pintype "passive"))
      (node (ref "C29") (pin "1") (pinfunction "1_1") (pintype "passive"))
      (node (ref "C30") (pin "1") (pinfunction "1_1") (pintype "passive"))
      (node (ref "C31") (pin "1") (pinfunction "1_1") (pintype "passive"))
      (node (ref "C34") (pin "1") (pinfunction "1_1") (pintype "passive"))
      (node (ref "C35") (pin "1") (pinfunction "1_1") (pintype "passive"))
      (node (ref "C36") (pin "1") (pinfunction "1_1") (pintype "passive"))
      (node (ref "C4") (pin "1") (pinfunction "1_1") (pintype "passive"))
      (node (ref "C40") (pin "1") (pinfunction "1_1") (pintype "passive"))
      (node (ref "C41") (pin "1") (pinfunction "1_1") (pintype "passive"))
      (node (ref "C42") (pin "1") (pinfunction "1_1") (pintype "passive"))
      (node (ref "C45") (pin "1") (pinfunction "1_1") (pintype "passive"))
      (node (ref "C46") (pin "1") (pinfunction "1_1") (pintype "passive"))
      (node (ref "C47") (pin "1") (pinfunction "1_1") (pintype "passive"))
      (node (ref "C5") (pin "1") (pinfunction "1_1") (pintype "passive"))
      (node (ref "C50") (pin "1") (pinfunction "1_1") (pintype "passive"))
      (node (ref "C51") (pin "1") (pinfunction "1_1") (pintype "passive"))
      (node (ref "C6") (pin "1") (pinfunction "1_1") (pintype "passive"))
      (node (ref "C9") (pin "1") (pinfunction "1_1") (pintype "passive"))
      (node (ref "L12") (pin "2") (pinfunction "B_2") (pintype "passive"))
      (node (ref "L15") (pin "2") (pinfunction "B_2") (pintype "passive"))
      (node (ref "L18") (pin "2") (pinfunction "B_2") (pintype "passive"))
      (node (ref "L21") (pin "2") (pinfunction "B_2") (pintype "passive"))
      (node (ref "L24") (pin "2") (pinfunction "B_2") (pintype "passive"))
      (node (ref "L27") (pin "2") (pinfunction "B_2") (pintype "passive"))
      (node (ref "L29") (pin "2") (pinfunction "B_2") (pintype "passive"))
      (node (ref "L3") (pin "2") (pinfunction "B_2") (pintype "passive"))
      (node (ref "L6") (pin "2") (pinfunction "B_2") (pintype "passive"))
      (node (ref "L9") (pin "2") (pinfunction "B_2") (pintype "passive"))
    )
    (net (code "20") (name "Net-(K6-NO_1)") (class "Default")
      (node (ref "K6") (pin "5") (pinfunction "NO_1_5") (pintype "passive"))
      (node (ref "K6") (pin "8") (pinfunction "NO_2_8") (pintype "passive"))
      (node (ref "L4") (pin "1") (pinfunction "A_1") (pintype "passive"))
    )
    (net (code "21") (name "Net-(K7-NO_1)") (class "Default")
      (node (ref "K7") (pin "5") (pinfunction "NO_1_5") (pintype "passive"))
      (node (ref "K7") (pin "8") (pinfunction "NO_2_8") (pintype "passive"))
      (node (ref "L5") (pin "2") (pinfunction "B_2") (pintype "passive"))
    )
    (net (code "22") (name "Net-(K8-NO_1)") (class "Default")
      (node (ref "K8") (pin "5") (pinfunction "NO_1_5") (pintype "passive"))
      (node (ref "K8") (pin "8") (pinfunction "NO_2_8") (pintype "passive"))
      (node (ref "L7") (pin "1") (pinfunction "A_1") (pintype "passive"))
    )
    (net (code "23") (name "Net-(K9-NO_1)") (class "Default")
      (node (ref "K9") (pin "5") (pinfunction "NO_1_5") (pintype "passive"))
      (node (ref "K9") (pin "8") (pinfunction "NO_2_8") (pintype "passive"))
      (node (ref "L8") (pin "2") (pinfunction "B_2") (pintype "passive"))
    )
    (net (code "24") (name "Net-(K10-NO_1)") (class "Default")
      (node (ref "K10") (pin "5") (pinfunction "NO_1_5") (pintype "passive"))
      (node (ref "K10") (pin "8") (pinfunction "NO_2_8") (pintype "passive"))
      (node (ref "L10") (pin "1") (pinfunction "A_1") (pintype "passive"))
    )
    (net (code "25") (name "Net-(K11-NO_1)") (class "Default")
      (node (ref "K11") (pin "5") (pinfunction "NO_1_5") (pintype "passive"))
      (node (ref "K11") (pin "8") (pinfunction "NO_2_8") (pintype "passive"))
      (node (ref "L11") (pin "2") (pinfunction "B_2") (pintype "passive"))
    )
    (net (code "26") (name "Net-(K12-NO_1)") (class "Default")
      (node (ref "K12") (pin "5") (pinfunction "NO_1_5") (pintype "passive"))
      (node (ref "K12") (pin "8") (pinfunction "NO_2_8") (pintype "passive"))
      (node (ref "L13") (pin "1") (pinfunction "A_1") (pintype "passive"))
    )
    (net (code "27") (name "Net-(K13-NO_1)") (class "Default")
      (node (ref "K13") (pin "5") (pinfunction "NO_1_5") (pintype "passive"))
      (node (ref "K13") (pin "8") (pinfunction "NO_2_8") (pintype "passive"))
      (node (ref "L14") (pin "2") (pinfunction "B_2") (pintype "passive"))
    )
    (net (code "28") (name "Net-(K14-NO_1)") (class "Default")
      (node (ref "K14") (pin "5") (pinfunction "NO_1_5") (pintype "passive"))
      (node (ref "K14") (pin "8") (pinfunction "NO_2_8") (pintype "passive"))
      (node (ref "L16") (pin "1") (pinfunction "A_1") (pintype "passive"))
    )
    (net (code "29") (name "Net-(K15-NO_1)") (class "Default")
      (node (ref "K15") (pin "5") (pinfunction "NO_1_5") (pintype "passive"))
      (node (ref "K15") (pin "8") (pinfunction "NO_2_8") (pintype "passive"))
      (node (ref "L17") (pin "2") (pinfunction "B_2") (pintype "passive"))
    )
    (net (code "30") (name "Net-(K16-NO_1)") (class "Default")
      (node (ref "K16") (pin "5") (pinfunction "NO_1_5") (pintype "passive"))
      (node (ref "K16") (pin "8") (pinfunction "NO_2_8") (pintype "passive"))
      (node (ref "L19") (pin "1") (pinfunction "A_1") (pintype "passive"))
    )
    (net (code "31") (name "Net-(K17-NO_1)") (class "Default")
      (node (ref "K17") (pin "5") (pinfunction "NO_1_5") (pintype "passive"))
      (node (ref "K17") (pin "8") (pinfunction "NO_2_8") (pintype "passive"))
      (node (ref "L20") (pin "2") (pinfunction "B_2") (pintype "passive"))
    )
    (net (code "32") (name "Net-(K18-NO_1)") (class "Default")
      (node (ref "K18") (pin "5") (pinfunction "NO_1_5") (pintype "passive"))
      (node (ref "K18") (pin "8") (pinfunction "NO_2_8") (pintype "passive"))
      (node (ref "L22") (pin "1") (pinfunction "A_1") (pintype "passive"))
    )
    (net (code "33") (name "Net-(K19-NO_1)") (class "Default")
      (node (ref "K19") (pin "5") (pinfunction "NO_1_5") (pintype "passive"))
      (node (ref "K19") (pin "8") (pinfunction "NO_2_8") (pintype "passive"))
      (node (ref "L23") (pin "2") (pinfunction "B_2") (pintype "passive"))
    )
    (net (code "34") (name "Net-(K20-NO_1)") (class "Default")
      (node (ref "K20") (pin "5") (pinfunction "NO_1_5") (pintype "passive"))
      (node (ref "K20") (pin "8") (pinfunction "NO_2_8") (pintype "passive"))
      (node (ref "L25") (pin "1") (pinfunction "A_1") (pintype "passive"))
    )
    (net (code "35") (name "Net-(K21-NO_1)") (class "Default")
      (node (ref "K21") (pin "5") (pinfunction "NO_1_5") (pintype "passive"))
      (node (ref "K21") (pin "8") (pinfunction "NO_2_8") (pintype "passive"))
      (node (ref "L26") (pin "2") (pinfunction "B_2") (pintype "passive"))
    )
    (net (code "36") (name "Net-(K22-NO_1)") (class "Default")
      (node (ref "K22") (pin "5") (pinfunction "NO_1_5") (pintype "passive"))
      (node (ref "K22") (pin "8") (pinfunction "NO_2_8") (pintype "passive"))
      (node (ref "L40") (pin "1") (pinfunction "A_1") (pintype "passive"))
    )
    (net (code "37") (name "Net-(K23-NO_1)") (class "Default")
      (node (ref "K23") (pin "5") (pinfunction "NO_1_5") (pintype "passive"))
      (node (ref "K23") (pin "8") (pinfunction "NO_2_8") (pintype "passive"))
      (node (ref "L28") (pin "2") (pinfunction "B_2") (pintype "passive"))
    )
    (net (code "38") (name "Net-(L1-B)") (class "Default")
      (node (ref "C2") (pin "2") (pinfunction "2_2") (pintype "passive"))
      (node (ref "C4") (pin "2") (pinfunction "2_2") (pintype "passive"))
      (node (ref "L1") (pin "2") (pinfunction "B_2") (pintype "passive"))
    )
    (net (code "39") (name "Net-(L2-A)") (class "Default")
      (node (ref "C3") (pin "1") (pinfunction "1_1") (pintype "passive"))
      (node (ref "C6") (pin "2") (pinfunction "2_2") (pintype "passive"))
      (node (ref "L2") (pin "1") (pinfunction "A_1") (pintype "passive"))
    )
    (net (code "40") (name "Net-(L3-A)") (class "Default")
      (node (ref "C2") (pin "1") (pinfunction "1_1") (pintype "passive"))
      (node (ref "C3") (pin "2") (pinfunction "2_2") (pintype "passive"))
      (node (ref "C5") (pin "2") (pinfunction "2_2") (pintype "passive"))
      (node (ref "L3") (pin "1") (pinfunction "A_1") (pintype "passive"))
    )
    (net (code "41") (name "Net-(L4-B)") (class "Default")
      (node (ref "C7") (pin "2") (pinfunction "2_2") (pintype "passive"))
      (node (ref "C9") (pin "2") (pinfunction "2_2") (pintype "passive"))
      (node (ref "L4") (pin "2") (pinfunction "B_2") (pintype "passive"))
    )
    (net (code "42") (name "Net-(L5-A)") (class "Default")
      (node (ref "C11") (pin "2") (pinfunction "2_2") (pintype "passive"))
      (node (ref "C8") (pin "1") (pinfunction "1_1") (pintype "passive"))
      (node (ref "L5") (pin "1") (pinfunction "A_1") (pintype "passive"))
    )
    (net (code "43") (name "Net-(L6-A)") (class "Default")
      (node (ref "C10") (pin "2") (pinfunction "2_2") (pintype "passive"))
      (node (ref "C7") (pin "1") (pinfunction "1_1") (pintype "passive"))
      (node (ref "C8") (pin "2") (pinfunction "2_2") (pintype "passive"))
      (node (ref "L6") (pin "1") (pinfunction "A_1") (pintype "passive"))
    )
    (net (code "44") (name "Net-(L7-B)") (class "Default")
      (node (ref "C12") (pin "2") (pinfunction "2_2") (pintype "passive"))
      (node (ref "C14") (pin "2") (pinfunction "2_2") (pintype "passive"))
      (node (ref "L7") (pin "2") (pinfunction "B_2") (pintype "passive"))
    )
    (net (code "45") (name "Net-(L8-A)") (class "Default")
      (node (ref "C13") (pin "1") (pinfunction "1_1") (pintype "passive"))
      (node (ref "C16") (pin "2") (pinfunction "2_2") (pintype "passive"))
      (node (ref "L8") (pin "1") (pinfunction "A_1") (pintype "passive"))
    )
    (net (code "46") (name "Net-(L9-A)") (class "Default")
      (node (ref "C12") (pin "1") (pinfunction "1_1") (pintype "passive"))
      (node (ref "C13") (pin "2") (pinfunction "2_2") (pintype "passive"))
      (node (ref "C15") (pin "2") (pinfunction "2_2") (pintype "passive"))
      (node (ref "L9") (pin "1") (pinfunction "A_1") (pintype "passive"))
    )
    (net (code "47") (name "Net-(L10-B)") (class "Default")
      (node (ref "C17") (pin "2") (pinfunction "2_2") (pintype "passive"))
      (node (ref "C19") (pin "2") (pinfunction "2_2") (pintype "passive"))
      (node (ref "L10") (pin "2") (pinfunction "B_2") (pintype "passive"))
    )
    (net (code "48") (name "Net-(L11-A)") (class "Default")
      (node (ref "C18") (pin "1") (pinfunction "1_1") (pintype "passive"))
      (node (ref "C21") (pin "2") (pinfunction "2_2") (pintype "passive"))
      (node (ref "L11") (pin "1") (pinfunction "A_1") (pintype "passive"))
    )
    (net (code "49") (name "Net-(L12-A)") (class "Default")
      (node (ref "C17") (pin "1") (pinfunction "1_1") (pintype "passive"))
      (node (ref "C18") (pin "2") (pinfunction "2_2") (pintype "passive"))
      (node (ref "C20") (pin "2") (pinfunction "2_2") (pintype "passive"))
      (node (ref "L12") (pin "1") (pinfunction "A_1") (pintype "passive"))
    )
    (net (code "50") (name "Net-(L13-B)") (class "Default")
      (node (ref "C22") (pin "2") (pinfunction "2_2") (pintype "passive"))
      (node (ref "C24") (pin "2") (pinfunction "2_2") (pintype "passive"))
      (node (ref "L13") (pin "2") (pinfunction "B_2") (pintype "passive"))
    )
    (net (code "51") (name "Net-(L14-A)") (class "Default")
      (node (ref "C23") (pin "1") (pinfunction "1_1") (pintype "passive"))
      (node (ref "C26") (pin "2") (pinfunction "2_2") (pintype "passive"))
      (node (ref "L14") (pin "1") (pinfunction "A_1") (pintype "passive"))
    )
    (net (code "52") (name "Net-(L15-A)") (class "Default")
      (node (ref "C22") (pin "1") (pinfunction "1_1") (pintype "passive"))
      (node (ref "C23") (pin "2") (pinfunction "2_2") (pintype "passive"))
      (node (ref "C25") (pin "2") (pinfunction "2_2") (pintype "passive"))
      (node (ref "L15") (pin "1") (pinfunction "A_1") (pintype "passive"))
    )
    (net (code "53") (name "Net-(L16-B)") (class "Default")
      (node (ref "C27") (pin "2") (pinfunction "2_2") (pintype "passive"))
      (node (ref "C29") (pin "2") (pinfunction "2_2") (pintype "passive"))
      (node (ref "L16") (pin "2") (pinfunction "B_2") (pintype "passive"))
    )
    (net (code "54") (name "Net-(L17-A)") (class "Default")
      (node (ref "C28") (pin "1") (pinfunction "1_1") (pintype "passive"))
      (node (ref "C31") (pin "2") (pinfunction "2_2") (pintype "passive"))
      (node (ref "L17") (pin "1") (pinfunction "A_1") (pintype "passive"))
    )
    (net (code "55") (name "Net-(L18-A)") (class "Default")
      (node (ref "C27") (pin "1") (pinfunction "1_1") (pintype "passive"))
      (node (ref "C28") (pin "2") (pinfunction "2_2") (pintype "passive"))
      (node (ref "C30") (pin "2") (pinfunction "2_2") (pintype "passive"))
      (node (ref "L18") (pin "1") (pinfunction "A_1") (pintype "passive"))
    )
    (net (code "56") (name "Net-(L19-B)") (class "Default")
      (node (ref "C32") (pin "2") (pinfunction "2_2") (pintype "passive"))
      (node (ref "C34") (pin "2") (pinfunction "2_2") (pintype "passive"))
      (node (ref "L19") (pin "2") (pinfunction "B_2") (pintype "passive"))
    )
    (net (code "57") (name "Net-(L20-A)") (class "Default")
      (node (ref "C33") (pin "1") (pinfunction "1_1") (pintype "passive"))
      (node (ref "C36") (pin "2") (pinfunction "2_2") (pintype "passive"))
      (node (ref "L20") (pin "1") (pinfunction "A_1") (pintype "passive"))
    )
    (net (code "58") (name "Net-(L21-A)") (class "Default")
      (node (ref "C32") (pin "1") (pinfunction "1_1") (pintype "passive"))
      (node (ref "C33") (pin "2") (pinfunction "2_2") (pintype "passive"))
      (node (ref "C35") (pin "2") (pinfunction "2_2") (pintype "passive"))
      (node (ref "L21") (pin "1") (pinfunction "A_1") (pintype "passive"))
    )
    (net (code "59") (name "Net-(L22-B)") (class "Default")
      (node (ref "C37") (pin "2") (pinfunction "2_2") (pintype "passive"))
      (node (ref "C40") (pin "2") (pinfunction "2_2") (pintype "passive"))
      (node (ref "L22") (pin "2") (pinfunction "B_2") (pintype "passive"))
    )
    (net (code "60") (name "Net-(L23-A)") (class "Default")
      (node (ref "C39") (pin "1") (pinfunction "1_1") (pintype "passive"))
      (node (ref "C42") (pin "2") (pinfunction "2_2") (pintype "passive"))
      (node (ref "L23") (pin "1") (pinfunction "A_1") (pintype "passive"))
    )
    (net (code "61") (name "Net-(L24-A)") (class "Default")
      (node (ref "C37") (pin "1") (pinfunction "1_1") (pintype "passive"))
      (node (ref "C39") (pin "2") (pinfunction "2_2") (pintype "passive"))
      (node (ref "C41") (pin "2") (pinfunction "2_2") (pintype "passive"))
      (node (ref "L24") (pin "1") (pinfunction "A_1") (pintype "passive"))
    )
    (net (code "62") (name "Net-(L25-B)") (class "Default")
      (node (ref "C43") (pin "2") (pinfunction "2_2") (pintype "passive"))
      (node (ref "C45") (pin "2") (pinfunction "2_2") (pintype "passive"))
      (node (ref "L25") (pin "2") (pinfunction "B_2") (pintype "passive"))
    )
    (net (code "63") (name "Net-(L26-A)") (class "Default")
      (node (ref "C44") (pin "1") (pinfunction "1_1") (pintype "passive"))
      (node (ref "C47") (pin "2") (pinfunction "2_2") (pintype "passive"))
      (node (ref "L26") (pin "1") (pinfunction "A_1") (pintype "passive"))
    )
    (net (code "64") (name "Net-(L27-A)") (class "Default")
      (node (ref "C43") (pin "1") (pinfunction "1_1") (pintype "passive"))
      (node (ref "C44") (pin "2") (pinfunction "2_2") (pintype "passive"))
      (node (ref "C46") (pin "2") (pinfunction "2_2") (pintype "passive"))
      (node (ref "L27") (pin "1") (pinfunction "A_1") (pintype "passive"))
    )
    (net (code "65") (name "Net-(L28-A)") (class "Default")
      (node (ref "C49") (pin "1") (pinfunction "1_1") (pintype "passive"))
      (node (ref "C51") (pin "2") (pinfunction "2_2") (pintype "passive"))
      (node (ref "L28") (pin "1") (pinfunction "A_1") (pintype "passive"))
    )
    (net (code "66") (name "Net-(L29-A)") (class "Default")
      (node (ref "C48") (pin "1") (pinfunction "1_1") (pintype "passive"))
      (node (ref "C49") (pin "2") (pinfunction "2_2") (pintype "passive"))
      (node (ref "C50") (pin "2") (pinfunction "2_2") (pintype "passive"))
      (node (ref "L29") (pin "1") (pinfunction "A_1") (pintype "passive"))
    )
    (net (code "67") (name "Net-(L40-B)") (class "Default")
      (node (ref "C1") (pin "2") (pinfunction "2_2") (pintype "passive"))
      (node (ref "C48") (pin "2") (pinfunction "2_2") (pintype "passive"))
      (node (ref "L40") (pin "2") (pinfunction "B_2") (pintype "passive"))
    )
    (net (code "68") (name "unconnected-(K6-NC_1-Pad3)") (class "Default")
      (node (ref "K6") (pin "3") (pinfunction "NC_1_3") (pintype "passive"))
    )
    (net (code "69") (name "unconnected-(K6-NC_2-Pad10)") (class "Default")
      (node (ref "K6") (pin "10") (pinfunction "NC_2_10") (pintype "passive"))
    )
    (net (code "70") (name "unconnected-(K7-NC_1-Pad3)") (class "Default")
      (node (ref "K7") (pin "3") (pinfunction "NC_1_3") (pintype "passive"))
    )
    (net (code "71") (name "unconnected-(K7-NC_2-Pad10)") (class "Default")
      (node (ref "K7") (pin "10") (pinfunction "NC_2_10") (pintype "passive"))
    )
    (net (code "72") (name "unconnected-(K8-NC_1-Pad3)") (class "Default")
      (node (ref "K8") (pin "3") (pinfunction "NC_1_3") (pintype "passive"))
    )
    (net (code "73") (name "unconnected-(K8-NC_2-Pad10)") (class "Default")
      (node (ref "K8") (pin "10") (pinfunction "NC_2_10") (pintype "passive"))
    )
    (net (code "74") (name "unconnected-(K9-NC_1-Pad3)") (class "Default")
      (node (ref "K9") (pin "3") (pinfunction "NC_1_3") (pintype "passive"))
    )
    (net (code "75") (name "unconnected-(K9-NC_2-Pad10)") (class "Default")
      (node (ref "K9") (pin "10") (pinfunction "NC_2_10") (pintype "passive"))
    )
    (net (code "76") (name "unconnected-(K10-NC_1-Pad3)") (class "Default")
      (node (ref "K10") (pin "3") (pinfunction "NC_1_3") (pintype "passive"))
    )
    (net (code "77") (name "unconnected-(K10-NC_2-Pad10)") (class "Default")
      (node (ref "K10") (pin "10") (pinfunction "NC_2_10") (pintype "passive"))
    )
    (net (code "78") (name "unconnected-(K11-NC_1-Pad3)") (class "Default")
      (node (ref "K11") (pin "3") (pinfunction "NC_1_3") (pintype "passive"))
    )
    (net (code "79") (name "unconnected-(K11-NC_2-Pad10)") (class "Default")
      (node (ref "K11") (pin "10") (pinfunction "NC_2_10") (pintype "passive"))
    )
    (net (code "80") (name "unconnected-(K12-NC_1-Pad3)") (class "Default")
      (node (ref "K12") (pin "3") (pinfunction "NC_1_3") (pintype "passive"))
    )
    (net (code "81") (name "unconnected-(K12-NC_2-Pad10)") (class "Default")
      (node (ref "K12") (pin "10") (pinfunction "NC_2_10") (pintype "passive"))
    )
    (net (code "82") (name "unconnected-(K13-NC_1-Pad3)") (class "Default")
      (node (ref "K13") (pin "3") (pinfunction "NC_1_3") (pintype "passive"))
    )
    (net (code "83") (name "unconnected-(K13-NC_2-Pad10)") (class "Default")
      (node (ref "K13") (pin "10") (pinfunction "NC_2_10") (pintype "passive"))
    )
    (net (code "84") (name "unconnected-(K14-NC_1-Pad3)") (class "Default")
      (node (ref "K14") (pin "3") (pinfunction "NC_1_3") (pintype "passive"))
    )
    (net (code "85") (name "unconnected-(K14-NC_2-Pad10)") (class "Default")
      (node (ref "K14") (pin "10") (pinfunction "NC_2_10") (pintype "passive"))
    )
    (net (code "86") (name "unconnected-(K15-NC_1-Pad3)") (class "Default")
      (node (ref "K15") (pin "3") (pinfunction "NC_1_3") (pintype "passive"))
    )
    (net (code "87") (name "unconnected-(K15-NC_2-Pad10)") (class "Default")
      (node (ref "K15") (pin "10") (pinfunction "NC_2_10") (pintype "passive"))
    )
    (net (code "88") (name "unconnected-(K16-NC_1-Pad3)") (class "Default")
      (node (ref "K16") (pin "3") (pinfunction "NC_1_3") (pintype "passive"))
    )
    (net (code "89") (name "unconnected-(K16-NC_2-Pad10)") (class "Default")
      (node (ref "K16") (pin "10") (pinfunction "NC_2_10") (pintype "passive"))
    )
    (net (code "90") (name "unconnected-(K17-NC_1-Pad3)") (class "Default")
      (node (ref "K17") (pin "3") (pinfunction "NC_1_3") (pintype "passive"))
    )
    (net (code "91") (name "unconnected-(K17-NC_2-Pad10)") (class "Default")
      (node (ref "K17") (pin "10") (pinfunction "NC_2_10") (pintype "passive"))
    )
    (net (code "92") (name "unconnected-(K18-NC_1-Pad3)") (class "Default")
      (node (ref "K18") (pin "3") (pinfunction "NC_1_3") (pintype "passive"))
    )
    (net (code "93") (name "unconnected-(K18-NC_2-Pad10)") (class "Default")
      (node (ref "K18") (pin "10") (pinfunction "NC_2_10") (pintype "passive"))
    )
    (net (code "94") (name "unconnected-(K19-NC_1-Pad3)") (class "Default")
      (node (ref "K19") (pin "3") (pinfunction "NC_1_3") (pintype "passive"))
    )
    (net (code "95") (name "unconnected-(K19-NC_2-Pad10)") (class "Default")
      (node (ref "K19") (pin "10") (pinfunction "NC_2_10") (pintype "passive"))
    )
    (net (code "96") (name "unconnected-(K20-NC_1-Pad3)") (class "Default")
      (node (ref "K20") (pin "3") (pinfunction "NC_1_3") (pintype "passive"))
    )
    (net (code "97") (name "unconnected-(K20-NC_2-Pad10)") (class "Default")
      (node (ref "K20") (pin "10") (pinfunction "NC_2_10") (pintype "passive"))
    )
    (net (code "98") (name "unconnected-(K21-NC_1-Pad3)") (class "Default")
      (node (ref "K21") (pin "3") (pinfunction "NC_1_3") (pintype "passive"))
    )
    (net (code "99") (name "unconnected-(K21-NC_2-Pad10)") (class "Default")
      (node (ref "K21") (pin "10") (pinfunction "NC_2_10") (pintype "passive"))
    )
    (net (code "100") (name "unconnected-(K22-NC_1-Pad3)") (class "Default")
      (node (ref "K22") (pin "3") (pinfunction "NC_1_3") (pintype "passive"))
    )
    (net (code "101") (name "unconnected-(K22-NC_2-Pad10)") (class "Default")
      (node (ref "K22") (pin "10") (pinfunction "NC_2_10") (pintype "passive"))
    )
    (net (code "102") (name "unconnected-(K23-NC_1-Pad3)") (class "Default")
      (node (ref "K23") (pin "3") (pinfunction "NC_1_3") (pintype "passive"))
    )
    (net (code "103") (name "unconnected-(K23-NC_2-Pad10)") (class "Default")
      (node (ref "K23") (pin "10") (pinfunction "NC_2_10") (pintype "passive"))
    )
  )
)
